# Hypera.net
KiCad netlist of a schematic drawn in EAGLE
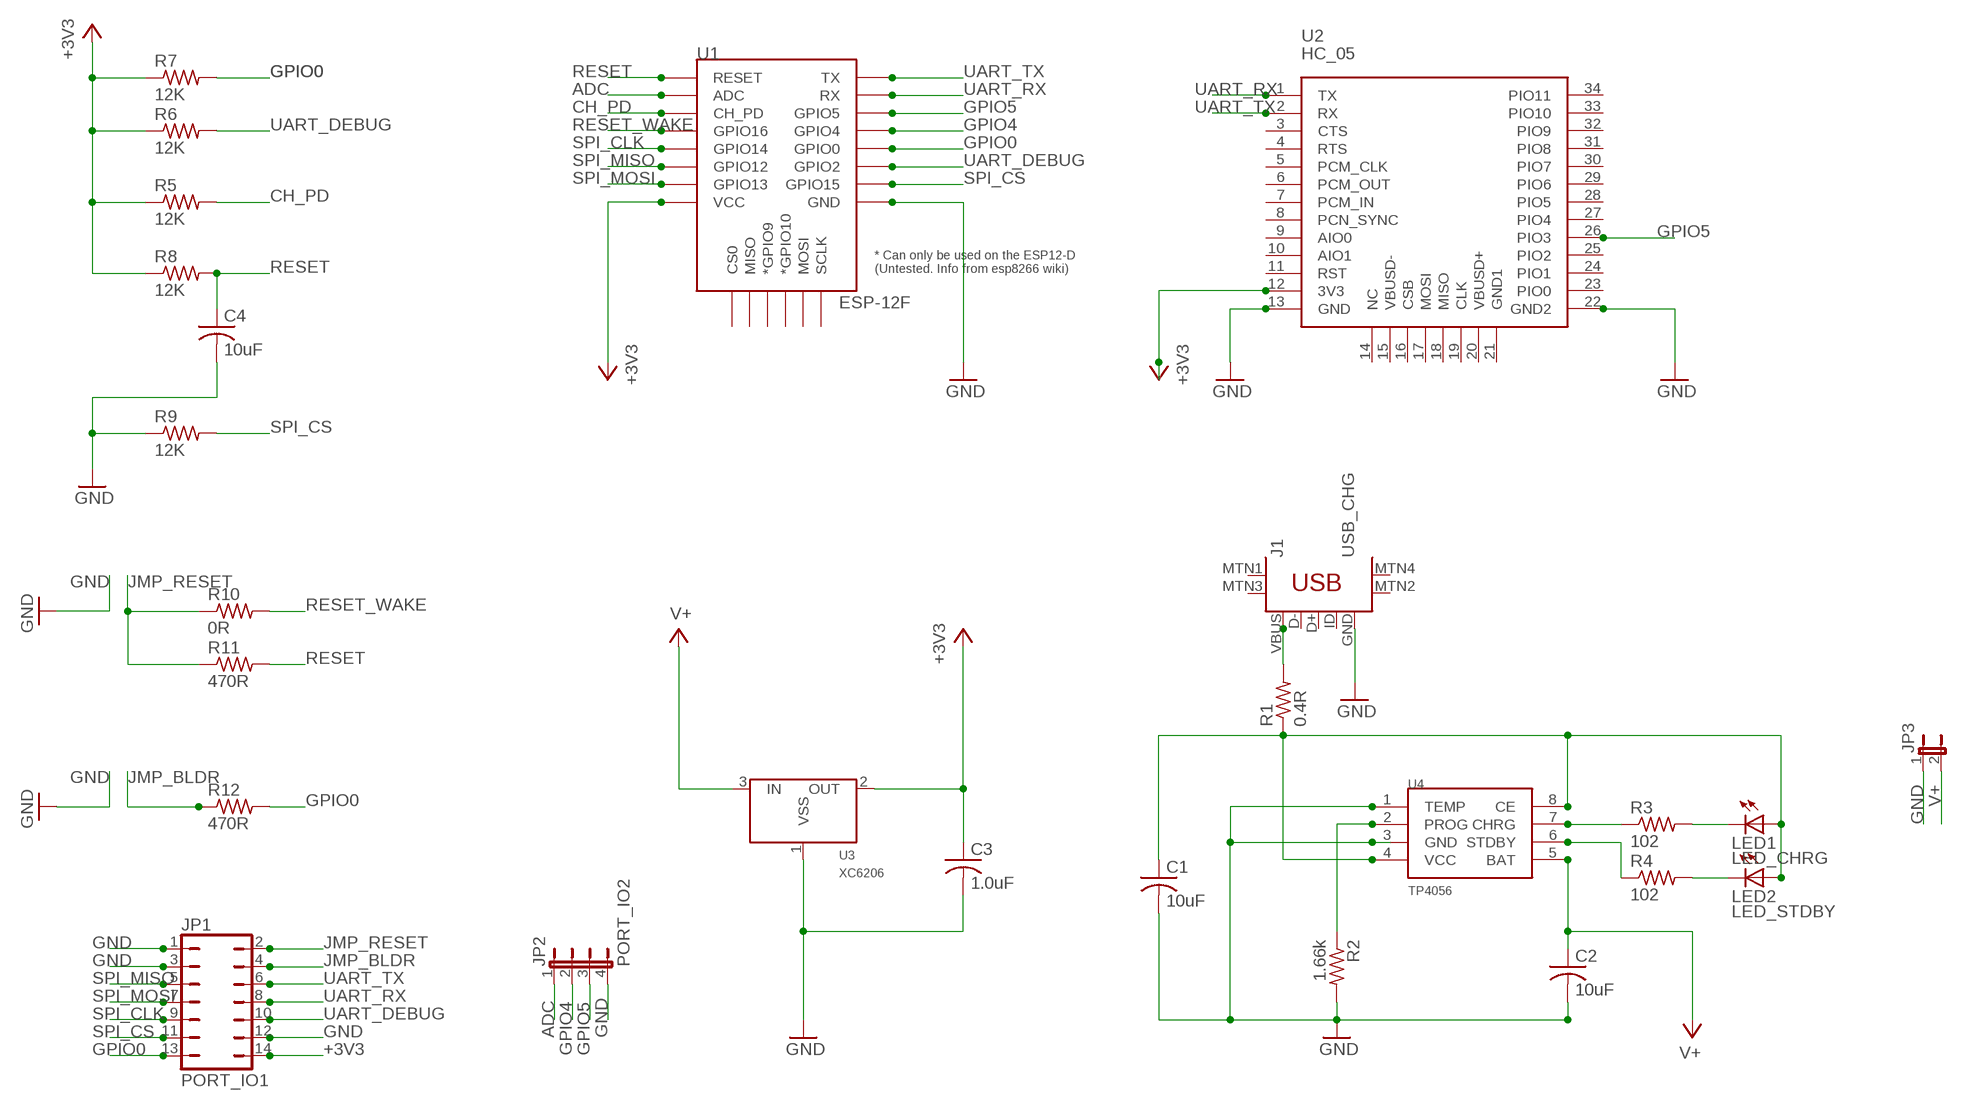
[diagram p0: schematic, sheet 1]

(export (version "E")
  (design (tool "Eeschema 10.0.6"))
  (components
    (comp (ref "C1")
      (value "10uF")
      (footprint "eagle-import:C0805")
      (libsource (lib "eagle-import") (part "C-USC0805"))
    )
    (comp (ref "C2")
      (value "10uF")
      (footprint "eagle-import:C0805")
      (libsource (lib "eagle-import") (part "C-USC0805"))
    )
    (comp (ref "C3")
      (value "1.0uF")
      (footprint "eagle-import:C0805K")
      (libsource (lib "eagle-import") (part "C-USC0805K"))
    )
    (comp (ref "C4")
      (value "10uF")
      (footprint "eagle-import:C0805")
      (libsource (lib "eagle-import") (part "C-USC0805"))
    )
    (comp (ref "J1")
      (value "USB_CHG")
      (footprint "eagle-import:USB-MINIB")
      (libsource (lib "eagle-import") (part "USB-MINIB-5PIN"))
    )
    (comp (ref "JP1")
      (value "PORT_IO1")
      (footprint "eagle-import:JP7Q")
      (libsource (lib "eagle-import") (part "JP7Q"))
    )
    (comp (ref "JP2")
      (value "PORT_IO2")
      (footprint "eagle-import:JP4")
      (libsource (lib "eagle-import") (part "JP4E"))
    )
    (comp (ref "JP3")
      (value "JP1E")
      (footprint "eagle-import:JP1")
      (libsource (lib "eagle-import") (part "JP1E"))
    )
    (comp (ref "LED1")
      (value "LED_CHRG")
      (footprint "eagle-import:CHIPLED_0805")
      (libsource (lib "eagle-import") (part "LEDCHIPLED_0805"))
    )
    (comp (ref "LED2")
      (value "LED_STDBY")
      (footprint "eagle-import:CHIPLED_0805")
      (libsource (lib "eagle-import") (part "LEDCHIPLED_0805"))
    )
    (comp (ref "R1")
      (value "0.4R")
      (footprint "eagle-import:R1210")
      (libsource (lib "eagle-import") (part "resistor_R-US_R1210"))
    )
    (comp (ref "R2")
      (value "1.66k")
      (footprint "eagle-import:M0805")
      (libsource (lib "eagle-import") (part "resistor_R-US_M0805"))
    )
    (comp (ref "R3")
      (value "102")
      (footprint "eagle-import:M0805")
      (libsource (lib "eagle-import") (part "resistor_R-US_M0805"))
    )
    (comp (ref "R4")
      (value "102")
      (footprint "eagle-import:M0805")
      (libsource (lib "eagle-import") (part "resistor_R-US_M0805"))
    )
    (comp (ref "R5")
      (value "12K")
      (footprint "eagle-import:R0805")
      (libsource (lib "eagle-import") (part "R-US_R0805"))
    )
    (comp (ref "R6")
      (value "12K")
      (footprint "eagle-import:R0805")
      (libsource (lib "eagle-import") (part "R-US_R0805"))
    )
    (comp (ref "R7")
      (value "12K")
      (footprint "eagle-import:R0805")
      (libsource (lib "eagle-import") (part "R-US_R0805"))
    )
    (comp (ref "R8")
      (value "12K")
      (footprint "eagle-import:R0805")
      (libsource (lib "eagle-import") (part "R-US_R0805"))
    )
    (comp (ref "R9")
      (value "12K")
      (footprint "eagle-import:R0805")
      (libsource (lib "eagle-import") (part "R-US_R0805"))
    )
    (comp (ref "R10")
      (value "0R")
      (footprint "eagle-import:R0805")
      (libsource (lib "eagle-import") (part "R-US_R0805"))
    )
    (comp (ref "R11")
      (value "470R")
      (footprint "eagle-import:R0805")
      (libsource (lib "eagle-import") (part "R-US_R0805"))
    )
    (comp (ref "R12")
      (value "470R")
      (footprint "eagle-import:R0805")
      (libsource (lib "eagle-import") (part "R-US_R0805"))
    )
    (comp (ref "U1")
      (value "ESP-12F")
      (footprint "eagle-import:ESP12E-SMD")
      (libsource (lib "eagle-import") (part "ESP12ESMD"))
    )
    (comp (ref "U2")
      (value "HC_05")
      (footprint "eagle-import:BLUETOOTH_SMD")
      (libsource (lib "eagle-import") (part "HC_05"))
    )
    (comp (ref "U3")
      (value "XC6206")
      (footprint "eagle-import:XC6206_SOT-23")
      (libsource (lib "eagle-import") (part "XC6206SOT-23"))
    )
    (comp (ref "U4")
      (value "TP4056")
      (footprint "eagle-import:SOP-8")
      (libsource (lib "eagle-import") (part "TP4056"))
    )
  )
  (nets
    (net (code "1") (name "+3V3") (class "Default")
      (node (ref "C3") (pin "1") (pinfunction "1_1") (pintype "passive"))
      (node (ref "JP1") (pin "14") (pinfunction "14_14") (pintype "passive"))
      (node (ref "R5") (pin "1") (pinfunction "1_1") (pintype "passive"))
      (node (ref "R6") (pin "1") (pinfunction "1_1") (pintype "passive"))
      (node (ref "R7") (pin "1") (pinfunction "1_1") (pintype "passive"))
      (node (ref "R8") (pin "1") (pinfunction "1_1") (pintype "passive"))
      (node (ref "U1") (pin "VCC") (pinfunction "VCC_VCC") (pintype "bidirectional"))
      (node (ref "U2") (pin "12") (pinfunction "3V3_12") (pintype "bidirectional"))
      (node (ref "U3") (pin "2") (pinfunction "OUT_2") (pintype "bidirectional"))
    )
    (net (code "2") (name "/ADC") (class "Default")
      (node (ref "JP2") (pin "1") (pinfunction "1_1") (pintype "passive"))
      (node (ref "U1") (pin "ADC") (pinfunction "ADC_ADC") (pintype "bidirectional"))
    )
    (net (code "3") (name "/CH_PD") (class "Default")
      (node (ref "R5") (pin "2") (pinfunction "2_2") (pintype "passive"))
      (node (ref "U1") (pin "CH_PD") (pinfunction "CH_PD_CH_PD") (pintype "bidirectional"))
    )
    (net (code "4") (name "/GPIO0") (class "Default")
      (node (ref "JP1") (pin "13") (pinfunction "13_13") (pintype "passive"))
      (node (ref "R12") (pin "2") (pinfunction "2_2") (pintype "passive"))
      (node (ref "R7") (pin "2") (pinfunction "2_2") (pintype "passive"))
      (node (ref "U1") (pin "GPIO0") (pinfunction "GPIO0_GPIO0") (pintype "bidirectional"))
    )
    (net (code "5") (name "/GPIO4") (class "Default")
      (node (ref "JP2") (pin "2") (pinfunction "2_2") (pintype "passive"))
      (node (ref "U1") (pin "GPIO4") (pinfunction "GPIO4_GPIO4") (pintype "bidirectional"))
    )
    (net (code "6") (name "/GPIO5") (class "Default")
      (node (ref "JP2") (pin "3") (pinfunction "3_3") (pintype "passive"))
      (node (ref "U1") (pin "GPIO5") (pinfunction "GPIO5_GPIO5") (pintype "bidirectional"))
      (node (ref "U2") (pin "26") (pinfunction "PIO3_26") (pintype "bidirectional"))
    )
    (net (code "7") (name "/JMP_BLDR") (class "Default")
      (node (ref "JP1") (pin "4") (pinfunction "4_4") (pintype "passive"))
      (node (ref "R12") (pin "1") (pinfunction "1_1") (pintype "passive"))
    )
    (net (code "8") (name "/JMP_RESET") (class "Default")
      (node (ref "JP1") (pin "2") (pinfunction "2_2") (pintype "passive"))
      (node (ref "R10") (pin "1") (pinfunction "1_1") (pintype "passive"))
      (node (ref "R11") (pin "1") (pinfunction "1_1") (pintype "passive"))
    )
    (net (code "9") (name "/RESET") (class "Default")
      (node (ref "C4") (pin "1") (pinfunction "1_1") (pintype "passive"))
      (node (ref "R11") (pin "2") (pinfunction "2_2") (pintype "passive"))
      (node (ref "R8") (pin "2") (pinfunction "2_2") (pintype "passive"))
      (node (ref "U1") (pin "RESET") (pinfunction "RESET_RESET") (pintype "bidirectional"))
    )
    (net (code "10") (name "/RESET_WAKE") (class "Default")
      (node (ref "R10") (pin "2") (pinfunction "2_2") (pintype "passive"))
      (node (ref "U1") (pin "GPIO16") (pinfunction "GPIO16_GPIO16") (pintype "bidirectional"))
    )
    (net (code "11") (name "/SPI_CLK") (class "Default")
      (node (ref "JP1") (pin "9") (pinfunction "9_9") (pintype "passive"))
      (node (ref "U1") (pin "GPIO14") (pinfunction "GPIO14_GPIO14") (pintype "bidirectional"))
    )
    (net (code "12") (name "/SPI_CS") (class "Default")
      (node (ref "JP1") (pin "11") (pinfunction "11_11") (pintype "passive"))
      (node (ref "R9") (pin "2") (pinfunction "2_2") (pintype "passive"))
      (node (ref "U1") (pin "GPIO15") (pinfunction "GPIO15_GPIO15") (pintype "bidirectional"))
    )
    (net (code "13") (name "/SPI_MISO") (class "Default")
      (node (ref "JP1") (pin "5") (pinfunction "5_5") (pintype "passive"))
      (node (ref "U1") (pin "GPIO12") (pinfunction "GPIO12_GPIO12") (pintype "bidirectional"))
    )
    (net (code "14") (name "/SPI_MOSI") (class "Default")
      (node (ref "JP1") (pin "7") (pinfunction "7_7") (pintype "passive"))
      (node (ref "U1") (pin "GPIO13") (pinfunction "GPIO13_GPIO13") (pintype "bidirectional"))
    )
    (net (code "15") (name "/UART_DEBUG") (class "Default")
      (node (ref "JP1") (pin "10") (pinfunction "10_10") (pintype "passive"))
      (node (ref "R6") (pin "2") (pinfunction "2_2") (pintype "passive"))
      (node (ref "U1") (pin "GPIO2") (pinfunction "GPIO2_GPIO2") (pintype "bidirectional"))
    )
    (net (code "16") (name "/UART_RX") (class "Default")
      (node (ref "JP1") (pin "8") (pinfunction "8_8") (pintype "passive"))
      (node (ref "U1") (pin "RXD0") (pinfunction "RX_RXD0") (pintype "bidirectional"))
      (node (ref "U2") (pin "1") (pinfunction "TX_1") (pintype "bidirectional"))
    )
    (net (code "17") (name "/UART_TX") (class "Default")
      (node (ref "JP1") (pin "6") (pinfunction "6_6") (pintype "passive"))
      (node (ref "U1") (pin "TXD0") (pinfunction "TX_TXD0") (pintype "bidirectional"))
      (node (ref "U2") (pin "2") (pinfunction "RX_2") (pintype "bidirectional"))
    )
    (net (code "18") (name "GND") (class "Default")
      (node (ref "C1") (pin "2") (pinfunction "2_2") (pintype "passive"))
      (node (ref "C2") (pin "2") (pinfunction "2_2") (pintype "passive"))
      (node (ref "C3") (pin "2") (pinfunction "2_2") (pintype "passive"))
      (node (ref "C4") (pin "2") (pinfunction "2_2") (pintype "passive"))
      (node (ref "J1") (pin "GND") (pinfunction "GND_GND") (pintype "bidirectional"))
      (node (ref "JP1") (pin "1") (pinfunction "1_1") (pintype "passive"))
      (node (ref "JP1") (pin "12") (pinfunction "12_12") (pintype "passive"))
      (node (ref "JP1") (pin "3") (pinfunction "3_3") (pintype "passive"))
      (node (ref "JP2") (pin "4") (pinfunction "4_4") (pintype "passive"))
      (node (ref "JP3") (pin "1") (pinfunction "1_1") (pintype "passive"))
      (node (ref "R2") (pin "2") (pinfunction "2_2") (pintype "passive"))
      (node (ref "R9") (pin "1") (pinfunction "1_1") (pintype "passive"))
      (node (ref "U1") (pin "GND") (pinfunction "GND_GND") (pintype "bidirectional"))
      (node (ref "U2") (pin "13") (pinfunction "GND_13") (pintype "bidirectional"))
      (node (ref "U2") (pin "22") (pinfunction "GND2_22") (pintype "bidirectional"))
      (node (ref "U3") (pin "1") (pinfunction "VSS_1") (pintype "bidirectional"))
      (node (ref "U4") (pin "1") (pinfunction "TEMP_1") (pintype "bidirectional"))
      (node (ref "U4") (pin "3") (pinfunction "GND_3") (pintype "bidirectional"))
    )
    (net (code "19") (name "Net-(J1-PadVBUS)") (class "Default")
      (node (ref "J1") (pin "VBUS") (pinfunction "VBUS_VBUS") (pintype "bidirectional"))
      (node (ref "R1") (pin "2") (pinfunction "2_2") (pintype "passive"))
    )
    (net (code "20") (name "Net-(LED1-PadC)") (class "Default")
      (node (ref "LED1") (pin "C") (pinfunction "C_C") (pintype "passive"))
      (node (ref "R3") (pin "2") (pinfunction "2_2") (pintype "passive"))
    )
    (net (code "21") (name "Net-(LED2-PadC)") (class "Default")
      (node (ref "LED2") (pin "C") (pinfunction "C_C") (pintype "passive"))
      (node (ref "R4") (pin "2") (pinfunction "2_2") (pintype "passive"))
    )
    (net (code "22") (name "Net-(U4-CE)") (class "Default")
      (node (ref "C1") (pin "1") (pinfunction "1_1") (pintype "passive"))
      (node (ref "LED1") (pin "A") (pinfunction "A_A") (pintype "passive"))
      (node (ref "LED2") (pin "A") (pinfunction "A_A") (pintype "passive"))
      (node (ref "R1") (pin "1") (pinfunction "1_1") (pintype "passive"))
      (node (ref "U4") (pin "4") (pinfunction "VCC_4") (pintype "bidirectional"))
      (node (ref "U4") (pin "8") (pinfunction "CE_8") (pintype "bidirectional"))
    )
    (net (code "23") (name "Net-(U4-CHRG)") (class "Default")
      (node (ref "R3") (pin "1") (pinfunction "1_1") (pintype "passive"))
      (node (ref "U4") (pin "7") (pinfunction "CHRG_7") (pintype "bidirectional"))
    )
    (net (code "24") (name "Net-(U4-PROG)") (class "Default")
      (node (ref "R2") (pin "1") (pinfunction "1_1") (pintype "passive"))
      (node (ref "U4") (pin "2") (pinfunction "PROG_2") (pintype "bidirectional"))
    )
    (net (code "25") (name "Net-(U4-STDBY)") (class "Default")
      (node (ref "R4") (pin "1") (pinfunction "1_1") (pintype "passive"))
      (node (ref "U4") (pin "6") (pinfunction "STDBY_6") (pintype "bidirectional"))
    )
    (net (code "26") (name "V+") (class "Default")
      (node (ref "C2") (pin "1") (pinfunction "1_1") (pintype "passive"))
      (node (ref "JP3") (pin "2") (pinfunction "2_2") (pintype "passive"))
      (node (ref "U3") (pin "3") (pinfunction "IN_3") (pintype "bidirectional"))
      (node (ref "U4") (pin "5") (pinfunction "BAT_5") (pintype "bidirectional"))
    )
    (net (code "27") (name "unconnected-(J1-MTN1-PadMTN3)") (class "Default")
      (node (ref "J1") (pin "MTN3") (pinfunction "MTN1_MTN3") (pintype "bidirectional"))
    )
    (net (code "28") (name "unconnected-(J1-MTN2-PadMTN1)") (class "Default")
      (node (ref "J1") (pin "MTN1") (pinfunction "MTN2_MTN1") (pintype "bidirectional"))
    )
    (net (code "29") (name "unconnected-(J1-MTN3-PadMTN2)") (class "Default")
      (node (ref "J1") (pin "MTN2") (pinfunction "MTN3_MTN2") (pintype "bidirectional"))
    )
    (net (code "30") (name "unconnected-(J1-PadD+)") (class "Default")
      (node (ref "J1") (pin "D+") (pinfunction "D+_D+") (pintype "bidirectional"))
    )
    (net (code "31") (name "unconnected-(J1-PadD-)") (class "Default")
      (node (ref "J1") (pin "D-") (pinfunction "D-_D-") (pintype "bidirectional"))
    )
    (net (code "32") (name "unconnected-(J1-PadID)") (class "Default")
      (node (ref "J1") (pin "ID") (pinfunction "ID_ID") (pintype "bidirectional"))
    )
    (net (code "33") (name "unconnected-(J1-PadMTN4)") (class "Default")
      (node (ref "J1") (pin "MTN4") (pinfunction "MTN4_MTN4") (pintype "bidirectional"))
    )
    (net (code "34") (name "unconnected-(U1-*GPIO9-PadGPIO9)") (class "Default")
      (node (ref "U1") (pin "GPIO9") (pinfunction "*GPIO9_GPIO9") (pintype "bidirectional"))
    )
    (net (code "35") (name "unconnected-(U1-*GPIO10-PadGPIO10)") (class "Default")
      (node (ref "U1") (pin "GPIO10") (pinfunction "*GPIO10_GPIO10") (pintype "bidirectional"))
    )
    (net (code "36") (name "unconnected-(U1-PadCS0)") (class "Default")
      (node (ref "U1") (pin "CS0") (pinfunction "CS0_CS0") (pintype "bidirectional"))
    )
    (net (code "37") (name "unconnected-(U1-PadMISO)") (class "Default")
      (node (ref "U1") (pin "MISO") (pinfunction "MISO_MISO") (pintype "bidirectional"))
    )
    (net (code "38") (name "unconnected-(U1-PadMOSI)") (class "Default")
      (node (ref "U1") (pin "MOSI") (pinfunction "MOSI_MOSI") (pintype "bidirectional"))
    )
    (net (code "39") (name "unconnected-(U1-PadSCLK)") (class "Default")
      (node (ref "U1") (pin "SCLK") (pinfunction "SCLK_SCLK") (pintype "bidirectional"))
    )
    (net (code "40") (name "unconnected-(U2-AIO0-Pad9)") (class "Default")
      (node (ref "U2") (pin "9") (pinfunction "AIO0_9") (pintype "bidirectional"))
    )
    (net (code "41") (name "unconnected-(U2-AIO1-Pad10)") (class "Default")
      (node (ref "U2") (pin "10") (pinfunction "AIO1_10") (pintype "bidirectional"))
    )
    (net (code "42") (name "unconnected-(U2-CLK-Pad19)") (class "Default")
      (node (ref "U2") (pin "19") (pinfunction "CLK_19") (pintype "bidirectional"))
    )
    (net (code "43") (name "unconnected-(U2-CSB-Pad16)") (class "Default")
      (node (ref "U2") (pin "16") (pinfunction "CSB_16") (pintype "bidirectional"))
    )
    (net (code "44") (name "unconnected-(U2-CTS-Pad3)") (class "Default")
      (node (ref "U2") (pin "3") (pinfunction "CTS_3") (pintype "bidirectional"))
    )
    (net (code "45") (name "unconnected-(U2-GND1-Pad21)") (class "Default")
      (node (ref "U2") (pin "21") (pinfunction "GND1_21") (pintype "bidirectional"))
    )
    (net (code "46") (name "unconnected-(U2-MISO-Pad18)") (class "Default")
      (node (ref "U2") (pin "18") (pinfunction "MISO_18") (pintype "bidirectional"))
    )
    (net (code "47") (name "unconnected-(U2-MOSI-Pad17)") (class "Default")
      (node (ref "U2") (pin "17") (pinfunction "MOSI_17") (pintype "bidirectional"))
    )
    (net (code "48") (name "unconnected-(U2-NC-Pad14)") (class "Default")
      (node (ref "U2") (pin "14") (pinfunction "NC_14") (pintype "bidirectional"))
    )
    (net (code "49") (name "unconnected-(U2-PCM_CLK-Pad5)") (class "Default")
      (node (ref "U2") (pin "5") (pinfunction "PCM_CLK_5") (pintype "bidirectional"))
    )
    (net (code "50") (name "unconnected-(U2-PCM_IN-Pad7)") (class "Default")
      (node (ref "U2") (pin "7") (pinfunction "PCM_IN_7") (pintype "bidirectional"))
    )
    (net (code "51") (name "unconnected-(U2-PCM_OUT-Pad6)") (class "Default")
      (node (ref "U2") (pin "6") (pinfunction "PCM_OUT_6") (pintype "bidirectional"))
    )
    (net (code "52") (name "unconnected-(U2-PCN_SYNC-Pad8)") (class "Default")
      (node (ref "U2") (pin "8") (pinfunction "PCN_SYNC_8") (pintype "bidirectional"))
    )
    (net (code "53") (name "unconnected-(U2-PIO0-Pad23)") (class "Default")
      (node (ref "U2") (pin "23") (pinfunction "PIO0_23") (pintype "bidirectional"))
    )
    (net (code "54") (name "unconnected-(U2-PIO1-Pad24)") (class "Default")
      (node (ref "U2") (pin "24") (pinfunction "PIO1_24") (pintype "bidirectional"))
    )
    (net (code "55") (name "unconnected-(U2-PIO2-Pad25)") (class "Default")
      (node (ref "U2") (pin "25") (pinfunction "PIO2_25") (pintype "bidirectional"))
    )
    (net (code "56") (name "unconnected-(U2-PIO4-Pad27)") (class "Default")
      (node (ref "U2") (pin "27") (pinfunction "PIO4_27") (pintype "bidirectional"))
    )
    (net (code "57") (name "unconnected-(U2-PIO5-Pad28)") (class "Default")
      (node (ref "U2") (pin "28") (pinfunction "PIO5_28") (pintype "bidirectional"))
    )
    (net (code "58") (name "unconnected-(U2-PIO6-Pad29)") (class "Default")
      (node (ref "U2") (pin "29") (pinfunction "PIO6_29") (pintype "bidirectional"))
    )
    (net (code "59") (name "unconnected-(U2-PIO7-Pad30)") (class "Default")
      (node (ref "U2") (pin "30") (pinfunction "PIO7_30") (pintype "bidirectional"))
    )
    (net (code "60") (name "unconnected-(U2-PIO8-Pad31)") (class "Default")
      (node (ref "U2") (pin "31") (pinfunction "PIO8_31") (pintype "bidirectional"))
    )
    (net (code "61") (name "unconnected-(U2-PIO9-Pad32)") (class "Default")
      (node (ref "U2") (pin "32") (pinfunction "PIO9_32") (pintype "bidirectional"))
    )
    (net (code "62") (name "unconnected-(U2-PIO10-Pad33)") (class "Default")
      (node (ref "U2") (pin "33") (pinfunction "PIO10_33") (pintype "bidirectional"))
    )
    (net (code "63") (name "unconnected-(U2-PIO11-Pad34)") (class "Default")
      (node (ref "U2") (pin "34") (pinfunction "PIO11_34") (pintype "bidirectional"))
    )
    (net (code "64") (name "unconnected-(U2-RST-Pad11)") (class "Default")
      (node (ref "U2") (pin "11") (pinfunction "RST_11") (pintype "bidirectional"))
    )
    (net (code "65") (name "unconnected-(U2-RTS-Pad4)") (class "Default")
      (node (ref "U2") (pin "4") (pinfunction "RTS_4") (pintype "bidirectional"))
    )
    (net (code "66") (name "unconnected-(U2-VBUSD+-Pad20)") (class "Default")
      (node (ref "U2") (pin "20") (pinfunction "VBUSD+_20") (pintype "bidirectional"))
    )
    (net (code "67") (name "unconnected-(U2-VBUSD--Pad15)") (class "Default")
      (node (ref "U2") (pin "15") (pinfunction "VBUSD-_15") (pintype "bidirectional"))
    )
  )
)
